# EXM_Safety_Stop_-_Rev_A1.net
KiCad netlist of a schematic drawn in EAGLE
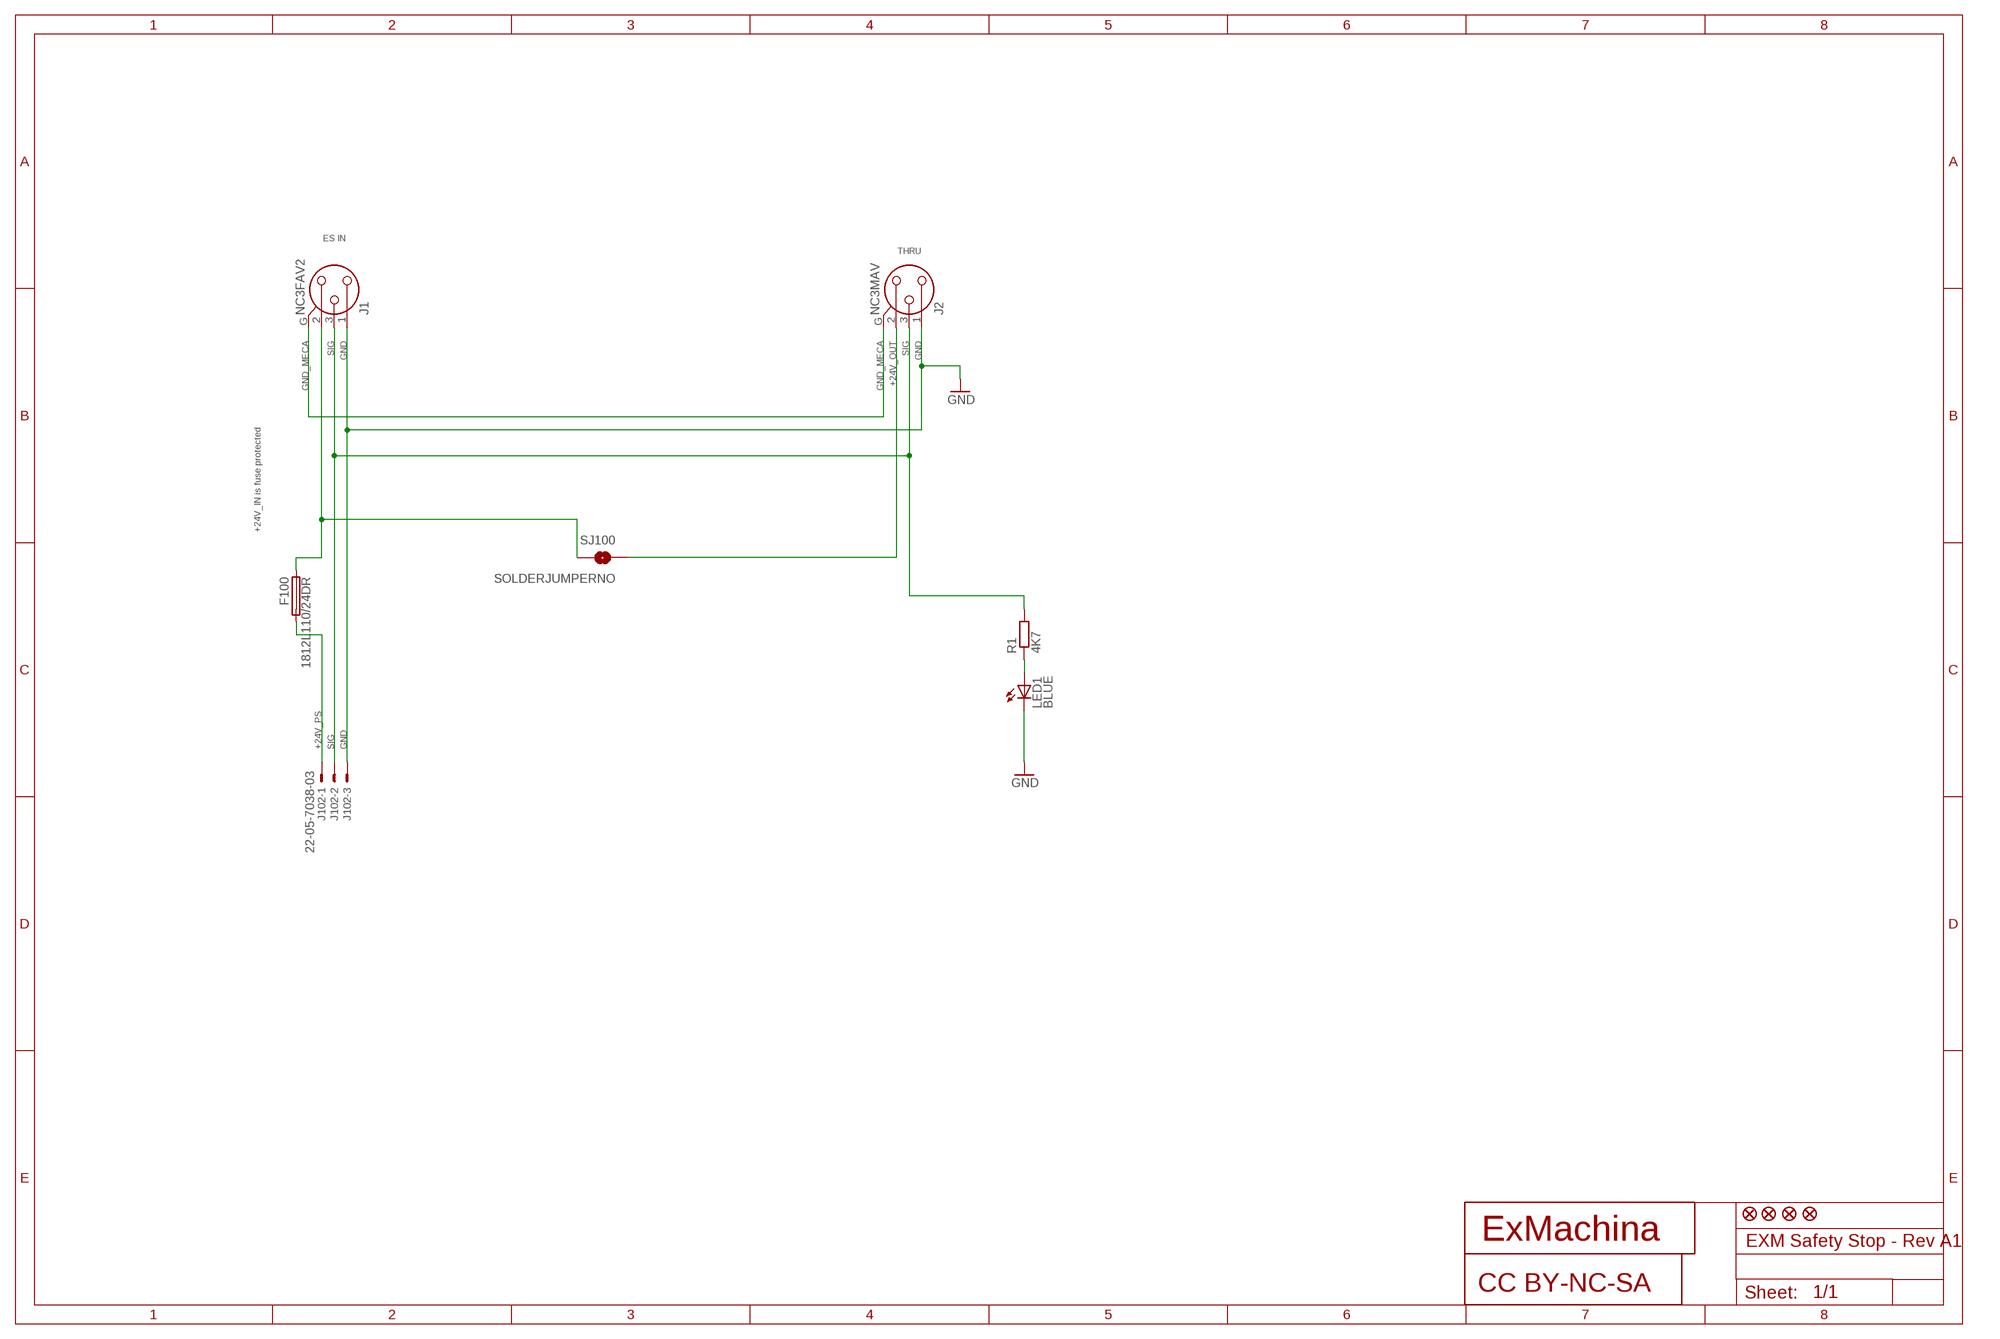
[diagram p0: schematic, sheet 1]

(export (version "E")
  (design (tool "Eeschema 10.0.6"))
  (components
    (comp (ref "CC100")
      (value "CC-BY-NC-SA")
      (footprint "eagle-import:CC-BY-NC-SA")
      (libsource (lib "eagle-import") (part "CC-BY-NC-SA"))
    )
    (comp (ref "F100")
      (value "1812L110/24DR")
      (footprint "eagle-import:LITTLEFUSE_SMD")
      (libsource (lib "eagle-import") (part "1812L110/24DR"))
    )
    (comp (ref "J1")
      (value "NC3FAV2")
      (footprint "eagle-import:NC3FAV2")
      (fields (field (name "MF") "NEUTRIK"))
      (libsource (lib "eagle-import") (part "NC3FAV2"))
    )
    (comp (ref "J2")
      (value "NC3MAV")
      (footprint "eagle-import:NC3MAV")
      (fields (field (name "MF") "FARNELL"))
      (libsource (lib "eagle-import") (part "NC3MAV"))
    )
    (comp (ref "J102")
      (value "22-05-7038-03")
      (footprint "eagle-import:7395-03")
      (libsource (lib "eagle-import") (part "22-?-0305-7038"))
    )
    (comp (ref "JP100")
      (value "FIDUCIAL1X2")
      (footprint "eagle-import:FIDUCIAL-1X2")
      (libsource (lib "eagle-import") (part "FIDUCIAL1X2"))
    )
    (comp (ref "JP101")
      (value "FIDUCIAL1X2")
      (footprint "eagle-import:FIDUCIAL-1X2")
      (libsource (lib "eagle-import") (part "FIDUCIAL1X2"))
    )
    (comp (ref "JP102")
      (value "FIDUCIAL1X2")
      (footprint "eagle-import:FIDUCIAL-1X2")
      (libsource (lib "eagle-import") (part "FIDUCIAL1X2"))
    )
    (comp (ref "JP103")
      (value "FIDUCIAL1X2")
      (footprint "eagle-import:FIDUCIAL-1X2")
      (libsource (lib "eagle-import") (part "FIDUCIAL1X2"))
    )
    (comp (ref "LED1")
      (value "BLUE")
      (footprint "eagle-import:CHIPLED_0603")
      (fields (field (name "MPN") "OVS-0603"))
      (libsource (lib "eagle-import") (part "LEDCHIPLED_0603"))
    )
    (comp (ref "R1")
      (value "4K7")
      (footprint "eagle-import:R0603")
      (fields (field (name "MPN") "RC0603FR-074K7L"))
      (libsource (lib "eagle-import") (part "R-EU_R0603"))
    )
    (comp (ref "SJ100")
      (value "SOLDERJUMPERNO")
      (footprint "eagle-import:SJ_2S-NO")
      (libsource (lib "eagle-import") (part "SOLDERJUMPERNO"))
    )
    (comp (ref "T100")
      (value "EXMACHINA-LOGO-NAME")
      (footprint "eagle-import:EXM-LOGO-BASELINE")
      (libsource (lib "eagle-import") (part "EXMACHINA-LOGO-NAME"))
    )
  )
  (nets
    (net (code "1") (name "/+24V_OUT") (class "Default")
      (node (ref "J2") (pin "2") (pinfunction "2_2") (pintype "passive"))
      (node (ref "SJ100") (pin "1") (pinfunction "1_1") (pintype "passive"))
    )
    (net (code "2") (name "/+24V_PS") (class "Default")
      (node (ref "F100") (pin "2") (pinfunction "2_2") (pintype "passive"))
      (node (ref "J102") (pin "1") (pinfunction "S_1") (pintype "passive"))
    )
    (net (code "3") (name "/GND_MECA") (class "Default")
      (node (ref "J1") (pin "G") (pinfunction "G_G") (pintype "passive"))
      (node (ref "J2") (pin "G") (pinfunction "G_G") (pintype "passive"))
    )
    (net (code "4") (name "/SIG") (class "Default")
      (node (ref "J1") (pin "3") (pinfunction "3_3") (pintype "passive"))
      (node (ref "J102") (pin "2") (pinfunction "S_2") (pintype "passive"))
      (node (ref "J2") (pin "3") (pinfunction "3_3") (pintype "passive"))
      (node (ref "R1") (pin "2") (pinfunction "2_2") (pintype "passive"))
    )
    (net (code "5") (name "GND") (class "Default")
      (node (ref "J1") (pin "1") (pinfunction "1_1") (pintype "passive"))
      (node (ref "J102") (pin "3") (pinfunction "S_3") (pintype "passive"))
      (node (ref "J2") (pin "1") (pinfunction "1_1") (pintype "passive"))
      (node (ref "LED1") (pin "C") (pinfunction "C_C") (pintype "passive"))
    )
    (net (code "6") (name "Net-(F100-Pad1)") (class "Default")
      (node (ref "F100") (pin "1") (pinfunction "1_1") (pintype "passive"))
      (node (ref "J1") (pin "2") (pinfunction "2_2") (pintype "passive"))
      (node (ref "SJ100") (pin "2") (pinfunction "2_2") (pintype "passive"))
    )
    (net (code "7") (name "Net-(LED1-PadA)") (class "Default")
      (node (ref "LED1") (pin "A") (pinfunction "A_A") (pintype "passive"))
      (node (ref "R1") (pin "1") (pinfunction "1_1") (pintype "passive"))
    )
  )
)
